# CPU.net
KiCad netlist of a schematic drawn in Altium Designer
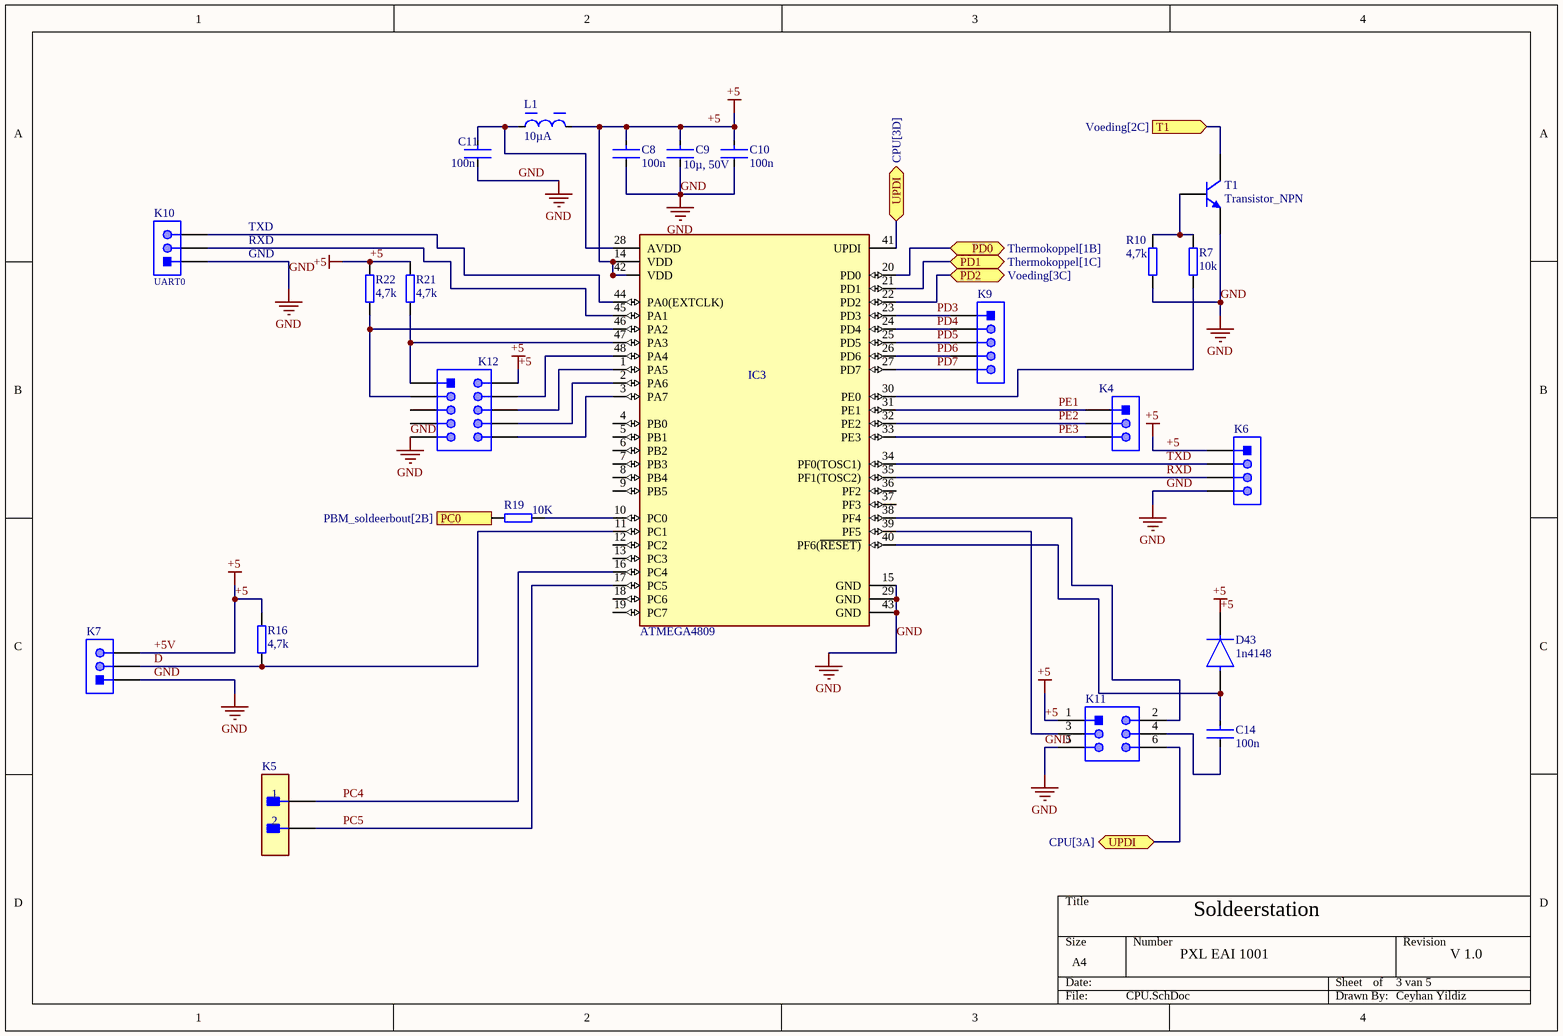
[diagram p0: CPU.SchDoc]

(export (version "E")
  (design (tool "Eeschema 10.0.6"))
  (components
    (comp (ref "C8")
      (value "100n")
      (footprint "CC_0805_L")
      (fields
        (field (name "MANUFACTURER") "KEMET")
        (field (name "OCTOPART") "https://octopart.com/c0805c224k5ractu-kemet-144670")
        (field (name "MANUFACTURER PART NUMBER") "C0805C224K5RACTU")
      )
      (libsource (lib "Schlib1") (part "Capacitor_Ceramic"))
    )
    (comp (ref "C9")
      (value "10µ, 50V")
      (footprint "CC_0805_L")
      (fields
        (field (name "MANUFACTURER") "KEMET")
        (field (name "OCTOPART") "https://octopart.com/c0805c224k5ractu-kemet-144670")
        (field (name "MANUFACTURER PART NUMBER") "C0805C224K5RACTU")
      )
      (libsource (lib "Schlib1") (part "Capacitor_Ceramic"))
    )
    (comp (ref "C10")
      (value "100n")
      (footprint "CC_0805_L")
      (fields
        (field (name "MANUFACTURER") "KEMET")
        (field (name "OCTOPART") "https://octopart.com/c0805c224k5ractu-kemet-144670")
        (field (name "MANUFACTURER PART NUMBER") "C0805C224K5RACTU")
      )
      (libsource (lib "Schlib1") (part "Capacitor_Ceramic"))
    )
    (comp (ref "C11")
      (value "100n")
      (footprint "CC_0805_L")
      (fields
        (field (name "MANUFACTURER") "KEMET")
        (field (name "OCTOPART") "https://octopart.com/c0805c224k5ractu-kemet-144670")
        (field (name "MANUFACTURER PART NUMBER") "C0805C224K5RACTU")
      )
      (libsource (lib "Schlib1") (part "Capacitor_Ceramic"))
    )
    (comp (ref "C14")
      (value "100n")
      (footprint "CC_0805_L")
      (fields
        (field (name "MANUFACTURER") "KEMET")
        (field (name "OCTOPART") "https://octopart.com/c0805c224k5ractu-kemet-144670")
        (field (name "MANUFACTURER PART NUMBER") "C0805C224K5RACTU")
      )
      (libsource (lib "Schlib1") (part "Capacitor_Ceramic"))
    )
    (comp (ref "D43")
      (value "1n4148")
      (footprint "SOD-123FL")
      (fields
        (field (name "MANUFACTURER PART NUMBER") "1N4007")
        (field (name "MANUFACTURER") "Diotec")
        (field (name "OCTOPART") "https://octopart.com/1n4007-diotec-4040411")
      )
      (libsource (lib "Schlib1") (part "Diode"))
    )
    (comp (ref "IC3")
      (value "ATMEGA4809")
      (footprint "TQFP_48_M")
      (libsource (lib "Schlib1") (part "ATMEGA4809"))
    )
    (comp (ref "K4")
      (value "61300311121")
      (footprint "pin header 1x3 - duplicate")
      (description "THT Vertical Pin Header WR-PHD, Pitch 2.54 mm, Single Row, 3 pins")
      (fields (field (name "MANUFACTURER") "Wurth Elektronik") (field (name "PUBLISHER") "WurthElektronik"))
      (libsource (lib "") (part "1x3_1"))
    )
    (comp (ref "K5")
      (value "M20-9990246")
      (footprint "pin header 1x2 - duplicate")
      (description "CONN HEADER VERT 2POS 2.54MM")
      (fields
        (field (name "OCTOPART") "https://octopart.com/m20-9990246-harwin-2590635")
        (field (name "MANUFACTURER") "Harwin")
      )
      (libsource (lib "Schlib1") (part "1x2"))
    )
    (comp (ref "K6")
      (value "61300411121")
      (footprint "pin header 1x4 - duplicate")
      (description "THT Vertical Pin Header WR-PHD, Pitch 2.54 mm, Single Row, 4 pins")
      (fields (field (name "MANUFACTURER") "Wurth Elektronik") (field (name "PUBLISHER") "WurthElektronik"))
      (libsource (lib "Schlib1") (part "1x4"))
    )
    (comp (ref "K7")
      (value "61300311121")
      (footprint "pin header 1x3 - duplicate")
      (description "THT Vertical Pin Header WR-PHD, Pitch 2.54 mm, Single Row, 3 pins")
      (fields (field (name "MANUFACTURER") "Wurth Elektronik") (field (name "PUBLISHER") "WurthElektronik"))
      (libsource (lib "Schlib1") (part "1x3"))
    )
    (comp (ref "K9")
      (value "61300511121")
      (footprint "pin header 1x5")
      (description "THT Vertical Pin Header WR-PHD, Pitch 2.54 mm, Single Row, 5 pins")
      (fields (field (name "MANUFACTURER") "Wurth Elektronik") (field (name "PUBLISHER") "WurthElektronik"))
      (libsource (lib "Schlib1") (part "1x5"))
    )
    (comp (ref "K10")
      (value "UART0")
      (footprint "pin header 1x3 - duplicate")
      (description "THT Vertical Pin Header WR-PHD, Pitch 2.54 mm, Single Row, 3 pins")
      (fields
        (field (name "PART NUMBER") "61300311121")
        (field (name "MANUFACTURER") "Wurth Elektronik")
        (field (name "PUBLISHER") "WurthElektronik")
      )
      (libsource (lib "Schlib1") (part "1x3"))
    )
    (comp (ref "K11")
      (value "61300621121")
      (footprint "pin header 2x6")
      (description "THT Vertical Pin Header WR-PHD, Pitch 2.54 mm, Dual Row, 6 pins")
      (fields (field (name "MANUFACTURER") "Wurth Elektronik") (field (name "PUBLISHER") "WurthElektronik"))
      (libsource (lib "Schlib1") (part "2x3"))
    )
    (comp (ref "K12")
      (value "61201021621")
      (footprint "box header 10-pin")
      (description "Male Box Header WR-BHD, THT, Vertical, pitch 2.54 mm, 10 pins")
      (fields (field (name "MANUFACTURER") "Wurth Elektronik") (field (name "PUBLISHER") "WurthElektronik"))
      (libsource (lib "Schlib1") (part "5x2"))
    )
    (comp (ref "L1")
      (value "10µA")
      (footprint "CC_0805_L")
      (fields (field (name "TOLERANCE") "20%"))
      (libsource (lib "Schlib1") (part "Choke"))
    )
    (comp (ref "R7")
      (value "10k")
      (footprint "R_0805_M")
      (fields (field (name "MANUFACTURER") "Vishay Dale") (field (name "PART NUMBER") "CRCW08050000Z0EA"))
      (libsource (lib "Schlib1") (part "Resistor"))
    )
    (comp (ref "R10")
      (value "4,7k")
      (footprint "R_0805_M")
      (fields (field (name "MANUFACTURER") "Vishay Dale") (field (name "PART NUMBER") "CRCW08050000Z0EA"))
      (libsource (lib "Schlib1") (part "Resistor"))
    )
    (comp (ref "R16")
      (value "4,7k")
      (footprint "R_0805_M")
      (fields (field (name "MANUFACTURER") "Vishay Dale") (field (name "PART NUMBER") "CRCW08050000Z0EA"))
      (libsource (lib "Schlib1") (part "Resistor"))
    )
    (comp (ref "R19")
      (value "10K")
      (footprint "R_0805_M")
      (fields (field (name "MANUFACTURER") "Vishay Dale") (field (name "PART NUMBER") "CRCW08050000Z0EA"))
      (libsource (lib "Schlib1") (part "Resistor"))
    )
    (comp (ref "R21")
      (value "4,7k")
      (footprint "R_0805_M")
      (fields (field (name "MANUFACTURER") "Vishay Dale") (field (name "PART NUMBER") "CRCW08050000Z0EA"))
      (libsource (lib "Schlib1") (part "Resistor"))
    )
    (comp (ref "R22")
      (value "4,7k")
      (footprint "R_0805_M")
      (fields (field (name "MANUFACTURER") "Vishay Dale") (field (name "PART NUMBER") "CRCW08050000Z0EA"))
      (libsource (lib "Schlib1") (part "Resistor"))
    )
    (comp (ref "T1")
      (value "Transistor_NPN")
      (footprint "SOT_23")
      (fields (field (name "MANUFACTURER") "On Semiconductor") (field (name "PARTNUMBER") "BC547C"))
      (libsource (lib "Schlib1") (part "Transistor_NPN"))
    )
  )
  (nets
    (net (code "1") (name "+5") (class "Default")
      (node (ref "C10") (pin "1") (pinfunction "1_1") (pintype "passive"))
      (node (ref "C8") (pin "1") (pinfunction "1_1") (pintype "passive"))
      (node (ref "C9") (pin "1") (pinfunction "1_1") (pintype "passive"))
      (node (ref "D43") (pin "1") (pinfunction "C_1") (pintype "passive"))
      (node (ref "IC3") (pin "14") (pinfunction "VDD_14") (pintype "power_in"))
      (node (ref "IC3") (pin "42") (pinfunction "VDD_42") (pintype "power_in"))
      (node (ref "K11") (pin "1") (pinfunction "1_1") (pintype "passive"))
      (node (ref "K12") (pin "2") (pinfunction "2_2") (pintype "passive"))
      (node (ref "K6") (pin "1") (pinfunction "1_1") (pintype "passive"))
      (node (ref "K7") (pin "3") (pinfunction "3_3") (pintype "passive"))
      (node (ref "L1") (pin "2") (pinfunction "2_2") (pintype "passive"))
      (node (ref "R16") (pin "2") (pinfunction "2_2") (pintype "passive"))
      (node (ref "R21") (pin "2") (pinfunction "2_2") (pintype "passive"))
      (node (ref "R22") (pin "2") (pinfunction "2_2") (pintype "passive"))
    )
    (net (code "2") (name "/D") (class "Default")
      (node (ref "IC3") (pin "11") (pinfunction "PC1_11") (pintype "bidirectional"))
      (node (ref "K7") (pin "2") (pinfunction "2_2") (pintype "passive"))
      (node (ref "R16") (pin "1") (pinfunction "1_1") (pintype "passive"))
    )
    (net (code "3") (name "/PC0") (class "Default")
      (node (ref "R19") (pin "1") (pinfunction "1_1") (pintype "passive"))
    )
    (net (code "4") (name "/PC4") (class "Default")
      (node (ref "IC3") (pin "16") (pinfunction "PC4_16") (pintype "bidirectional"))
      (node (ref "K5") (pin "1") (pinfunction "1_1") (pintype "passive"))
    )
    (net (code "5") (name "/PC5") (class "Default")
      (node (ref "IC3") (pin "17") (pinfunction "PC5_17") (pintype "bidirectional"))
      (node (ref "K5") (pin "2") (pinfunction "2_2") (pintype "passive"))
    )
    (net (code "6") (name "/PD0") (class "Default")
      (node (ref "IC3") (pin "20") (pinfunction "PD0_20") (pintype "bidirectional"))
    )
    (net (code "7") (name "/PD1") (class "Default")
      (node (ref "IC3") (pin "21") (pinfunction "PD1_21") (pintype "bidirectional"))
    )
    (net (code "8") (name "/PD2") (class "Default")
      (node (ref "IC3") (pin "22") (pinfunction "PD2_22") (pintype "bidirectional"))
    )
    (net (code "9") (name "/PD3") (class "Default")
      (node (ref "IC3") (pin "23") (pinfunction "PD3_23") (pintype "bidirectional"))
      (node (ref "K9") (pin "1") (pinfunction "1_1") (pintype "passive"))
    )
    (net (code "10") (name "/PD4") (class "Default")
      (node (ref "IC3") (pin "24") (pinfunction "PD4_24") (pintype "bidirectional"))
      (node (ref "K9") (pin "2") (pinfunction "2_2") (pintype "passive"))
    )
    (net (code "11") (name "/PD5") (class "Default")
      (node (ref "IC3") (pin "25") (pinfunction "PD5_25") (pintype "bidirectional"))
      (node (ref "K9") (pin "3") (pinfunction "3_3") (pintype "passive"))
    )
    (net (code "12") (name "/PD6") (class "Default")
      (node (ref "IC3") (pin "26") (pinfunction "PD6_26") (pintype "bidirectional"))
      (node (ref "K9") (pin "4") (pinfunction "4_4") (pintype "passive"))
    )
    (net (code "13") (name "/PD7") (class "Default")
      (node (ref "IC3") (pin "27") (pinfunction "PD7_27") (pintype "bidirectional"))
      (node (ref "K9") (pin "5") (pinfunction "5_5") (pintype "passive"))
    )
    (net (code "14") (name "/PE1") (class "Default")
      (node (ref "IC3") (pin "31") (pinfunction "PE1_31") (pintype "bidirectional"))
      (node (ref "K4") (pin "1") (pinfunction "1_1") (pintype "passive"))
    )
    (net (code "15") (name "/PE2") (class "Default")
      (node (ref "IC3") (pin "32") (pinfunction "PE2_32") (pintype "bidirectional"))
      (node (ref "K4") (pin "2") (pinfunction "2_2") (pintype "passive"))
    )
    (net (code "16") (name "/PE3") (class "Default")
      (node (ref "IC3") (pin "33") (pinfunction "PE3_33") (pintype "bidirectional"))
      (node (ref "K4") (pin "3") (pinfunction "3_3") (pintype "passive"))
    )
    (net (code "17") (name "/RXD") (class "Default")
      (node (ref "IC3") (pin "35") (pinfunction "PF1(TOSC2)_35") (pintype "bidirectional"))
      (node (ref "K6") (pin "3") (pinfunction "3_3") (pintype "passive"))
    )
    (net (code "18") (name "/T1") (class "Default")
      (node (ref "T1") (pin "1") (pinfunction "C_1") (pintype "passive"))
    )
    (net (code "19") (name "/TXD") (class "Default")
      (node (ref "IC3") (pin "34") (pinfunction "PF0(TOSC1)_34") (pintype "bidirectional"))
      (node (ref "K6") (pin "2") (pinfunction "2_2") (pintype "passive"))
    )
    (net (code "20") (name "/UPDI") (class "Default")
      (node (ref "IC3") (pin "41") (pinfunction "UPDI_41") (pintype "passive"))
      (node (ref "K11") (pin "6") (pinfunction "6_6") (pintype "passive"))
    )
    (net (code "21") (name "GND") (class "Default")
      (node (ref "C10") (pin "2") (pinfunction "2_2") (pintype "passive"))
      (node (ref "C11") (pin "2") (pinfunction "2_2") (pintype "passive"))
      (node (ref "C8") (pin "2") (pinfunction "2_2") (pintype "passive"))
      (node (ref "C9") (pin "2") (pinfunction "2_2") (pintype "passive"))
      (node (ref "IC3") (pin "15") (pinfunction "GND_15") (pintype "open_emitter"))
      (node (ref "IC3") (pin "29") (pinfunction "GND_29") (pintype "power_in"))
      (node (ref "IC3") (pin "43") (pinfunction "GND_43") (pintype "power_in"))
      (node (ref "K10") (pin "1") (pinfunction "1_1") (pintype "passive"))
      (node (ref "K11") (pin "5") (pinfunction "5_5") (pintype "passive"))
      (node (ref "K12") (pin "9") (pinfunction "9_9") (pintype "passive"))
      (node (ref "K6") (pin "4") (pinfunction "4_4") (pintype "passive"))
      (node (ref "K7") (pin "1") (pinfunction "1_1") (pintype "passive"))
      (node (ref "R10") (pin "1") (pinfunction "1_1") (pintype "passive"))
      (node (ref "T1") (pin "3") (pinfunction "E_3") (pintype "passive"))
    )
    (net (code "22") (name "Net-(C14-Pad2)") (class "Default")
      (node (ref "C14") (pin "2") (pinfunction "2_2") (pintype "passive"))
      (node (ref "K11") (pin "4") (pinfunction "4_4") (pintype "passive"))
    )
    (net (code "23") (name "Net-(D43-A)") (class "Default")
      (node (ref "C14") (pin "1") (pinfunction "1_1") (pintype "passive"))
      (node (ref "D43") (pin "2") (pinfunction "A_2") (pintype "passive"))
      (node (ref "IC3") (pin "40") (pinfunction "PF6(~{RESET)}_40") (pintype "bidirectional"))
    )
    (net (code "24") (name "Net-(IC3-AVDD)") (class "Default")
      (node (ref "C11") (pin "1") (pinfunction "1_1") (pintype "passive"))
      (node (ref "IC3") (pin "28") (pinfunction "AVDD_28") (pintype "power_in"))
      (node (ref "L1") (pin "1") (pinfunction "1_1") (pintype "passive"))
    )
    (net (code "25") (name "Net-(IC3-PA0(EXTCLK))") (class "Default")
      (node (ref "IC3") (pin "44") (pinfunction "PA0(EXTCLK)_44") (pintype "bidirectional"))
      (node (ref "K10") (pin "3") (pinfunction "3_3") (pintype "passive"))
    )
    (net (code "26") (name "Net-(IC3-PA1)") (class "Default")
      (node (ref "IC3") (pin "45") (pinfunction "PA1_45") (pintype "bidirectional"))
      (node (ref "K10") (pin "2") (pinfunction "2_2") (pintype "passive"))
    )
    (net (code "27") (name "Net-(IC3-PA2)") (class "Default")
      (node (ref "IC3") (pin "46") (pinfunction "PA2_46") (pintype "bidirectional"))
      (node (ref "K12") (pin "3") (pinfunction "3_3") (pintype "passive"))
      (node (ref "R22") (pin "1") (pinfunction "1_1") (pintype "passive"))
    )
    (net (code "28") (name "Net-(IC3-PA3)") (class "Default")
      (node (ref "IC3") (pin "47") (pinfunction "PA3_47") (pintype "bidirectional"))
      (node (ref "K12") (pin "1") (pinfunction "1_1") (pintype "passive"))
      (node (ref "R21") (pin "1") (pinfunction "1_1") (pintype "passive"))
    )
    (net (code "29") (name "Net-(IC3-PA4)") (class "Default")
      (node (ref "IC3") (pin "48") (pinfunction "PA4_48") (pintype "bidirectional"))
      (node (ref "K12") (pin "4") (pinfunction "4_4") (pintype "passive"))
    )
    (net (code "30") (name "Net-(IC3-PA5)") (class "Default")
      (node (ref "IC3") (pin "1") (pinfunction "PA5_1") (pintype "bidirectional"))
      (node (ref "K12") (pin "6") (pinfunction "6_6") (pintype "passive"))
    )
    (net (code "31") (name "Net-(IC3-PA6)") (class "Default")
      (node (ref "IC3") (pin "2") (pinfunction "PA6_2") (pintype "bidirectional"))
      (node (ref "K12") (pin "8") (pinfunction "8_8") (pintype "passive"))
    )
    (net (code "32") (name "Net-(IC3-PA7)") (class "Default")
      (node (ref "IC3") (pin "3") (pinfunction "PA7_3") (pintype "bidirectional"))
      (node (ref "K12") (pin "10") (pinfunction "10_10") (pintype "passive"))
    )
    (net (code "33") (name "Net-(IC3-PC0)") (class "Default")
      (node (ref "IC3") (pin "10") (pinfunction "PC0_10") (pintype "bidirectional"))
      (node (ref "R19") (pin "2") (pinfunction "2_2") (pintype "passive"))
    )
    (net (code "34") (name "Net-(IC3-PE0)") (class "Default")
      (node (ref "IC3") (pin "30") (pinfunction "PE0_30") (pintype "bidirectional"))
      (node (ref "R7") (pin "1") (pinfunction "1_1") (pintype "passive"))
    )
    (net (code "35") (name "Net-(IC3-PF4)") (class "Default")
      (node (ref "IC3") (pin "38") (pinfunction "PF4_38") (pintype "bidirectional"))
      (node (ref "K11") (pin "2") (pinfunction "2_2") (pintype "passive"))
    )
    (net (code "36") (name "Net-(IC3-PF5)") (class "Default")
      (node (ref "IC3") (pin "39") (pinfunction "PF5_39") (pintype "bidirectional"))
      (node (ref "K11") (pin "3") (pinfunction "3_3") (pintype "passive"))
    )
    (net (code "37") (name "Net-(T1-B)") (class "Default")
      (node (ref "R10") (pin "2") (pinfunction "2_2") (pintype "passive"))
      (node (ref "R7") (pin "2") (pinfunction "2_2") (pintype "passive"))
      (node (ref "T1") (pin "2") (pinfunction "B_2") (pintype "passive"))
    )
    (net (code "38") (name "unconnected-(IC3-PB0-Pad4)") (class "Default")
      (node (ref "IC3") (pin "4") (pinfunction "PB0_4") (pintype "bidirectional"))
    )
    (net (code "39") (name "unconnected-(IC3-PB1-Pad5)") (class "Default")
      (node (ref "IC3") (pin "5") (pinfunction "PB1_5") (pintype "bidirectional"))
    )
    (net (code "40") (name "unconnected-(IC3-PB2-Pad6)") (class "Default")
      (node (ref "IC3") (pin "6") (pinfunction "PB2_6") (pintype "bidirectional"))
    )
    (net (code "41") (name "unconnected-(IC3-PB3-Pad7)") (class "Default")
      (node (ref "IC3") (pin "7") (pinfunction "PB3_7") (pintype "bidirectional"))
    )
    (net (code "42") (name "unconnected-(IC3-PB4-Pad8)") (class "Default")
      (node (ref "IC3") (pin "8") (pinfunction "PB4_8") (pintype "bidirectional"))
    )
    (net (code "43") (name "unconnected-(IC3-PB5-Pad9)") (class "Default")
      (node (ref "IC3") (pin "9") (pinfunction "PB5_9") (pintype "bidirectional"))
    )
    (net (code "44") (name "unconnected-(IC3-PC2-Pad12)") (class "Default")
      (node (ref "IC3") (pin "12") (pinfunction "PC2_12") (pintype "bidirectional"))
    )
    (net (code "45") (name "unconnected-(IC3-PC3-Pad13)") (class "Default")
      (node (ref "IC3") (pin "13") (pinfunction "PC3_13") (pintype "bidirectional"))
    )
    (net (code "46") (name "unconnected-(IC3-PC6-Pad18)") (class "Default")
      (node (ref "IC3") (pin "18") (pinfunction "PC6_18") (pintype "bidirectional"))
    )
    (net (code "47") (name "unconnected-(IC3-PC7-Pad19)") (class "Default")
      (node (ref "IC3") (pin "19") (pinfunction "PC7_19") (pintype "bidirectional"))
    )
    (net (code "48") (name "unconnected-(IC3-PF2-Pad36)") (class "Default")
      (node (ref "IC3") (pin "36") (pinfunction "PF2_36") (pintype "bidirectional"))
    )
    (net (code "49") (name "unconnected-(IC3-PF3-Pad37)") (class "Default")
      (node (ref "IC3") (pin "37") (pinfunction "PF3_37") (pintype "bidirectional"))
    )
    (net (code "50") (name "unconnected-(K12-Pad5)") (class "Default")
      (node (ref "K12") (pin "5") (pinfunction "5_5") (pintype "passive"))
    )
    (net (code "51") (name "unconnected-(K12-Pad7)") (class "Default")
      (node (ref "K12") (pin "7") (pinfunction "7_7") (pintype "passive"))
    )
  )
)
